# ZOWI_Main_Board_Booster.net
KiCad netlist of a schematic drawn in Altium Designer
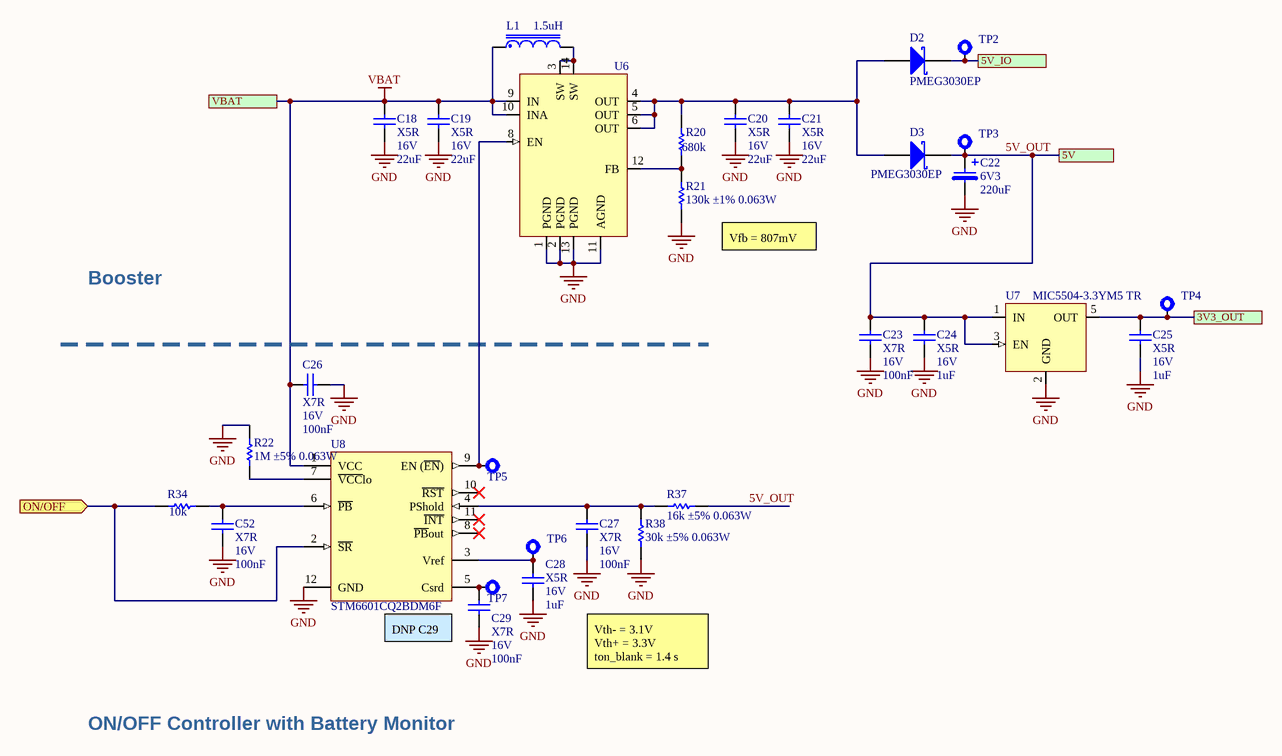
[diagram p0: ZOWI_Main_Board_Booster.SchDoc]

(export (version "E")
  (design (tool "Eeschema 10.0.6"))
  (components
    (comp (ref "C18")
      (value "Capacitor")
      (footprint "C0805")
      (description "Capacitor SMD")
      (fields
        (field (name "DIELECTRIC") "X5R")
        (field (name "VOLTAGE") "16V")
        (field (name "CAPACITANCE") "22uF")
        (field (name "PART NUMBER") "C0805_22uF_16V_±20%")
        (field (name "TOLERANCE") "±20%")
      )
      (libsource (lib "Pasives_Capacitor_SMD") (part "Capacitor"))
    )
    (comp (ref "C19")
      (value "Capacitor")
      (footprint "C0805")
      (description "Capacitor SMD")
      (fields
        (field (name "DIELECTRIC") "X5R")
        (field (name "VOLTAGE") "16V")
        (field (name "CAPACITANCE") "22uF")
        (field (name "PART NUMBER") "C0805_22uF_16V_±20%")
        (field (name "TOLERANCE") "±20%")
      )
      (libsource (lib "Pasives_Capacitor_SMD") (part "Capacitor"))
    )
    (comp (ref "C20")
      (value "Capacitor")
      (footprint "C0805")
      (description "Capacitor SMD")
      (fields
        (field (name "DIELECTRIC") "X5R")
        (field (name "VOLTAGE") "16V")
        (field (name "CAPACITANCE") "22uF")
        (field (name "PART NUMBER") "C0805_22uF_16V_±20%")
        (field (name "TOLERANCE") "±20%")
      )
      (libsource (lib "Pasives_Capacitor_SMD") (part "Capacitor"))
    )
    (comp (ref "C21")
      (value "Capacitor")
      (footprint "C0805")
      (description "Capacitor SMD")
      (fields
        (field (name "DIELECTRIC") "X5R")
        (field (name "VOLTAGE") "16V")
        (field (name "CAPACITANCE") "22uF")
        (field (name "PART NUMBER") "C0805_22uF_16V_±20%")
        (field (name "TOLERANCE") "±20%")
      )
      (libsource (lib "Pasives_Capacitor_SMD") (part "Capacitor"))
    )
    (comp (ref "C22")
      (value "Electrolytic")
      (footprint "CASE_D")
      (description "Capacitor, Electrolytic, SMD")
      (fields
        (field (name "VOLTAGE") "6V3")
        (field (name "CAPACITANCE") "220uF")
        (field (name "PART NUMBER") "Cap_Al_220uF_6V3")
        (field (name "MANUFACTURER") "Panasonic")
      )
      (libsource (lib "Pasives_Electrolytic_SMD") (part "Electrolytic"))
    )
    (comp (ref "C23")
      (value "Capacitor")
      (footprint "C0402")
      (description "Capacitor SMD")
      (fields
        (field (name "DIELECTRIC") "X7R")
        (field (name "VOLTAGE") "16V")
        (field (name "CAPACITANCE") "100nF")
        (field (name "PART NUMBER") "C0402_100nF_16V_±10%")
        (field (name "TOLERANCE") "±10%")
      )
      (libsource (lib "Pasives_Capacitor_SMD") (part "Capacitor"))
    )
    (comp (ref "C24")
      (value "Capacitor")
      (footprint "C0603")
      (description "Capacitor SMD")
      (fields
        (field (name "DIELECTRIC") "X5R")
        (field (name "VOLTAGE") "16V")
        (field (name "CAPACITANCE") "1uF")
        (field (name "PART NUMBER") "C0603_1uF_16V_±10%")
        (field (name "TOLERANCE") "±10%")
      )
      (libsource (lib "Pasives_Capacitor_SMD") (part "Capacitor"))
    )
    (comp (ref "C25")
      (value "Capacitor")
      (footprint "C0603")
      (description "Capacitor SMD")
      (fields
        (field (name "DIELECTRIC") "X5R")
        (field (name "VOLTAGE") "16V")
        (field (name "CAPACITANCE") "1uF")
        (field (name "PART NUMBER") "C0603_1uF_16V_±10%")
        (field (name "TOLERANCE") "±10%")
      )
      (libsource (lib "Pasives_Capacitor_SMD") (part "Capacitor"))
    )
    (comp (ref "C26")
      (value "Capacitor")
      (footprint "C0402")
      (description "Capacitor SMD")
      (fields
        (field (name "DIELECTRIC") "X7R")
        (field (name "VOLTAGE") "16V")
        (field (name "CAPACITANCE") "100nF")
        (field (name "PART NUMBER") "C0402_100nF_16V_±10%")
        (field (name "TOLERANCE") "±10%")
      )
      (libsource (lib "Pasives_Capacitor_SMD") (part "Capacitor"))
    )
    (comp (ref "C27")
      (value "Capacitor")
      (footprint "C0402")
      (description "Capacitor SMD")
      (fields
        (field (name "DIELECTRIC") "X7R")
        (field (name "VOLTAGE") "16V")
        (field (name "CAPACITANCE") "100nF")
        (field (name "PART NUMBER") "C0402_100nF_16V_±10%")
        (field (name "TOLERANCE") "±10%")
      )
      (libsource (lib "Pasives_Capacitor_SMD") (part "Capacitor"))
    )
    (comp (ref "C28")
      (value "Capacitor")
      (footprint "C0603")
      (description "Capacitor SMD")
      (fields
        (field (name "DIELECTRIC") "X5R")
        (field (name "VOLTAGE") "16V")
        (field (name "CAPACITANCE") "1uF")
        (field (name "PART NUMBER") "C0603_1uF_16V_±10%")
        (field (name "TOLERANCE") "±10%")
      )
      (libsource (lib "Pasives_Capacitor_SMD") (part "Capacitor"))
    )
    (comp (ref "C29")
      (value "Capacitor")
      (footprint "C0402")
      (description "Capacitor SMD")
      (fields
        (field (name "DIELECTRIC") "X7R")
        (field (name "VOLTAGE") "16V")
        (field (name "CAPACITANCE") "100nF")
        (field (name "PART NUMBER") "C0402_100nF_16V_±10%")
        (field (name "TOLERANCE") "±10%")
      )
      (libsource (lib "Pasives_Capacitor_SMD") (part "Capacitor"))
    )
    (comp (ref "C52")
      (value "Capacitor")
      (footprint "C0402")
      (description "Capacitor SMD")
      (fields
        (field (name "DIELECTRIC") "X7R")
        (field (name "VOLTAGE") "16V")
        (field (name "CAPACITANCE") "100nF")
        (field (name "PART NUMBER") "C0402_100nF_16V_±10%")
        (field (name "TOLERANCE") "±10%")
      )
      (libsource (lib "Pasives_Capacitor_SMD") (part "Capacitor"))
    )
    (comp (ref "D2")
      (value "PMEG3030EP")
      (footprint "SOD128")
      (description "Schottky Diode")
      (fields (field (name "MANUFACTURER") "NXP"))
      (libsource (lib "Semiconductors_Diodes") (part "Schottky"))
    )
    (comp (ref "D3")
      (value "PMEG3030EP")
      (footprint "SOD128")
      (description "Schottky Diode")
      (fields (field (name "MANUFACTURER") "NXP"))
      (libsource (lib "Semiconductors_Diodes") (part "Schottky"))
    )
    (comp (ref "L1")
      (value "SRN5040-1R5Y")
      (footprint "SRN5040")
      (description "Inductor, Power, SMD")
      (fields
        (field (name "PART NUMBER") "1.5uH_3,5A")
        (field (name "L") "1.5uH")
        (field (name "MANUFACTURER") "Bourns")
      )
      (libsource (lib "Pasivos_Inductor_SMD") (part "Power Inductor"))
    )
    (comp (ref "R20")
      (value "Resistor")
      (footprint "R0402")
      (description "Resistor, SMD")
      (fields
        (field (name "TOLERANCE") "±1%")
        (field (name "POWER") "0.063W")
        (field (name "RESISTANCE") "680k")
      )
      (libsource (lib "Pasives_Resistor_SMD") (part "Resistor"))
    )
    (comp (ref "R21")
      (value "130k ±1% 0.063W")
      (footprint "R0402")
      (description "Resistor, SMD")
      (fields (field (name "TOLERANCE") "±1%") (field (name "POWER") "0.063W"))
      (libsource (lib "Pasives_Resistor_SMD") (part "Resistor"))
    )
    (comp (ref "R22")
      (value "1M ±5% 0.063W")
      (footprint "R0402")
      (description "Resistor, SMD")
      (fields (field (name "TOLERANCE") "±5%") (field (name "POWER") "0.063W"))
      (libsource (lib "Pasives_Resistor_SMD") (part "Resistor"))
    )
    (comp (ref "R34")
      (value "Resistor")
      (footprint "R0402")
      (description "Resistor, SMD")
      (fields
        (field (name "TOLERANCE") "±5%")
        (field (name "POWER") "0.063W")
        (field (name "RESISTANCE") "10k")
      )
      (libsource (lib "Pasives_Resistor_SMD") (part "Resistor"))
    )
    (comp (ref "R37")
      (value "16k ±5% 0.063W")
      (footprint "R0402")
      (description "Resistor, SMD")
      (fields (field (name "TOLERANCE") "±5%") (field (name "POWER") "0.063W"))
      (libsource (lib "Pasives_Resistor_SMD") (part "Resistor"))
    )
    (comp (ref "R38")
      (value "30k ±5% 0.063W")
      (footprint "R0402")
      (description "Resistor, SMD")
      (fields (field (name "TOLERANCE") "±5%") (field (name "POWER") "0.063W"))
      (libsource (lib "Pasives_Resistor_SMD") (part "Resistor"))
    )
    (comp (ref "TP2")
      (value "Testpoint")
      (footprint "TP_SMD_1mm")
      (fields (field (name "MANUFACTURER") "Oxley") (field (name "PART NUMBER") "TP_SMD_1mm"))
      (libsource (lib "Miscelanea") (part "Testpoint"))
    )
    (comp (ref "TP3")
      (value "Testpoint")
      (footprint "TP_SMD_1mm")
      (fields (field (name "MANUFACTURER") "Oxley") (field (name "PART NUMBER") "TP_SMD_1mm"))
      (libsource (lib "Miscelanea") (part "Testpoint"))
    )
    (comp (ref "TP4")
      (value "Testpoint")
      (footprint "TP_SMD_1mm")
      (fields (field (name "MANUFACTURER") "Oxley") (field (name "PART NUMBER") "TP_SMD_1mm"))
      (libsource (lib "Miscelanea") (part "Testpoint"))
    )
    (comp (ref "TP5")
      (value "Testpoint")
      (footprint "TP_SMD_1mm")
      (fields (field (name "MANUFACTURER") "Oxley") (field (name "PART NUMBER") "TP_SMD_1mm"))
      (libsource (lib "Miscelanea") (part "Testpoint"))
    )
    (comp (ref "TP6")
      (value "Testpoint")
      (footprint "TP_SMD_1mm")
      (fields (field (name "MANUFACTURER") "Oxley") (field (name "PART NUMBER") "TP_SMD_1mm"))
      (libsource (lib "Miscelanea") (part "Testpoint"))
    )
    (comp (ref "TP7")
      (value "Testpoint")
      (footprint "TP_SMD_1mm")
      (fields (field (name "MANUFACTURER") "Oxley") (field (name "PART NUMBER") "TP_SMD_1mm"))
      (libsource (lib "Miscelanea") (part "Testpoint"))
    )
    (comp (ref "U6")
      (value "MP3421GG-Z")
      (footprint "QFN14_2X2")
      (description "Synchronous Boost Regulator with Bi-Directional Load Disconnect")
      (fields (field (name "PART NUMBER") "MP3421") (field (name "MANUFACTURER") "MPS"))
      (libsource (lib "Power_Regulator") (part "MP3421"))
    )
    (comp (ref "U7")
      (value "MIC5504-3.3YM5 TR")
      (footprint "SOT23-5")
      (description "LDO 300mA")
      (fields (field (name "PART NUMBER") "MIC5504-3.3") (field (name "MANUFACTURER") "Micrel"))
      (libsource (lib "Power_Regulator") (part "MIC550X"))
    )
    (comp (ref "U8")
      (value "STM6601")
      (footprint "TDFN12")
      (description "Smart push-button on/off controller")
      (fields
        (field (name "PART NUMBER") "STM6601CQ2BDM6F")
        (field (name "MANUFACTURER") "ST Microelectronics")
      )
      (libsource (lib "Power_Management") (part "STM6601"))
    )
  )
  (nets
    (net (code "1") (name "/3V3_OUT") (class "Default")
      (node (ref "C25") (pin "2") (pinfunction "2_2") (pintype "passive"))
      (node (ref "TP4") (pin "1") (pinfunction "1_1") (pintype "passive"))
      (node (ref "U7") (pin "5") (pinfunction "OUT_5") (pintype "passive"))
    )
    (net (code "2") (name "/5V_IO") (class "Default")
      (node (ref "D2") (pin "k") (pinfunction "K_k") (pintype "passive"))
      (node (ref "TP2") (pin "1") (pinfunction "1_1") (pintype "passive"))
    )
    (net (code "3") (name "/5V_OUT") (class "Default")
      (node (ref "C22") (pin "1") (pinfunction "1_1") (pintype "passive"))
      (node (ref "C23") (pin "2") (pinfunction "2_2") (pintype "passive"))
      (node (ref "C24") (pin "2") (pinfunction "2_2") (pintype "passive"))
      (node (ref "D3") (pin "k") (pinfunction "K_k") (pintype "passive"))
      (node (ref "R37") (pin "2") (pinfunction "2_2") (pintype "passive"))
      (node (ref "TP3") (pin "1") (pinfunction "1_1") (pintype "passive"))
      (node (ref "U7") (pin "1") (pinfunction "IN_1") (pintype "passive"))
      (node (ref "U7") (pin "3") (pinfunction "EN_3") (pintype "input"))
    )
    (net (code "4") (name "/ON{slash}OFF") (class "Default")
      (node (ref "R34") (pin "2") (pinfunction "2_2") (pintype "passive"))
      (node (ref "U8") (pin "2") (pinfunction "~{SR}_2") (pintype "input"))
    )
    (net (code "5") (name "GND") (class "Default")
      (node (ref "C18") (pin "1") (pinfunction "1_1") (pintype "passive"))
      (node (ref "C19") (pin "1") (pinfunction "1_1") (pintype "passive"))
      (node (ref "C20") (pin "1") (pinfunction "1_1") (pintype "passive"))
      (node (ref "C21") (pin "1") (pinfunction "1_1") (pintype "passive"))
      (node (ref "C22") (pin "2") (pinfunction "2_2") (pintype "passive"))
      (node (ref "C23") (pin "1") (pinfunction "1_1") (pintype "passive"))
      (node (ref "C24") (pin "1") (pinfunction "1_1") (pintype "passive"))
      (node (ref "C25") (pin "1") (pinfunction "1_1") (pintype "passive"))
      (node (ref "C26") (pin "2") (pinfunction "2_2") (pintype "passive"))
      (node (ref "C27") (pin "1") (pinfunction "1_1") (pintype "passive"))
      (node (ref "C28") (pin "1") (pinfunction "1_1") (pintype "passive"))
      (node (ref "C29") (pin "1") (pinfunction "1_1") (pintype "passive"))
      (node (ref "C52") (pin "1") (pinfunction "1_1") (pintype "passive"))
      (node (ref "R21") (pin "1") (pinfunction "1_1") (pintype "passive"))
      (node (ref "R22") (pin "1") (pinfunction "1_1") (pintype "passive"))
      (node (ref "R38") (pin "1") (pinfunction "1_1") (pintype "passive"))
      (node (ref "U6") (pin "1") (pinfunction "PGND_1") (pintype "passive"))
      (node (ref "U6") (pin "11") (pinfunction "AGND_11") (pintype "passive"))
      (node (ref "U6") (pin "13") (pinfunction "PGND_13") (pintype "passive"))
      (node (ref "U6") (pin "2") (pinfunction "PGND_2") (pintype "passive"))
      (node (ref "U7") (pin "2") (pinfunction "GND_2") (pintype "passive"))
      (node (ref "U8") (pin "12") (pinfunction "GND_12") (pintype "passive"))
    )
    (net (code "6") (name "Net-(C20-Pad2)") (class "Default")
      (node (ref "C20") (pin "2") (pinfunction "2_2") (pintype "passive"))
      (node (ref "C21") (pin "2") (pinfunction "2_2") (pintype "passive"))
      (node (ref "D2") (pin "A") (pinfunction "A_A") (pintype "passive"))
      (node (ref "D3") (pin "A") (pinfunction "A_A") (pintype "passive"))
      (node (ref "R20") (pin "2") (pinfunction "2_2") (pintype "passive"))
      (node (ref "U6") (pin "4") (pinfunction "OUT_4") (pintype "passive"))
      (node (ref "U6") (pin "5") (pinfunction "OUT_5") (pintype "passive"))
      (node (ref "U6") (pin "6") (pinfunction "OUT_6") (pintype "passive"))
    )
    (net (code "7") (name "Net-(L1-Pad2)") (class "Default")
      (node (ref "L1") (pin "2") (pinfunction "2_2") (pintype "passive"))
      (node (ref "U6") (pin "14") (pinfunction "SW_14") (pintype "passive"))
      (node (ref "U6") (pin "3") (pinfunction "SW_3") (pintype "passive"))
    )
    (net (code "8") (name "Net-(U6-EN)") (class "Default")
      (node (ref "TP5") (pin "1") (pinfunction "1_1") (pintype "passive"))
      (node (ref "U6") (pin "8") (pinfunction "EN_8") (pintype "input"))
      (node (ref "U8") (pin "9") (pinfunction "EN_(~{EN})_9") (pintype "output"))
    )
    (net (code "9") (name "Net-(U6-FB)") (class "Default")
      (node (ref "R20") (pin "1") (pinfunction "1_1") (pintype "passive"))
      (node (ref "R21") (pin "2") (pinfunction "2_2") (pintype "passive"))
      (node (ref "U6") (pin "12") (pinfunction "FB_12") (pintype "passive"))
    )
    (net (code "10") (name "Net-(U8-Csrd)") (class "Default")
      (node (ref "C29") (pin "2") (pinfunction "2_2") (pintype "passive"))
      (node (ref "TP7") (pin "1") (pinfunction "1_1") (pintype "passive"))
      (node (ref "U8") (pin "5") (pinfunction "Csrd_5") (pintype "passive"))
    )
    (net (code "11") (name "Net-(U8-PShold)") (class "Default")
      (node (ref "C27") (pin "2") (pinfunction "2_2") (pintype "passive"))
      (node (ref "R37") (pin "1") (pinfunction "1_1") (pintype "passive"))
      (node (ref "R38") (pin "2") (pinfunction "2_2") (pintype "passive"))
      (node (ref "U8") (pin "4") (pinfunction "PShold_4") (pintype "input"))
    )
    (net (code "12") (name "Net-(U8-Vref)") (class "Default")
      (node (ref "C28") (pin "2") (pinfunction "2_2") (pintype "passive"))
      (node (ref "TP6") (pin "1") (pinfunction "1_1") (pintype "passive"))
      (node (ref "U8") (pin "3") (pinfunction "Vref_3") (pintype "passive"))
    )
    (net (code "13") (name "Net-(U8-~{PB})") (class "Default")
      (node (ref "C52") (pin "2") (pinfunction "2_2") (pintype "passive"))
      (node (ref "R34") (pin "1") (pinfunction "1_1") (pintype "passive"))
      (node (ref "U8") (pin "6") (pinfunction "~{PB}_6") (pintype "input"))
    )
    (net (code "14") (name "Net-(U8-~{VCC}lo)") (class "Default")
      (node (ref "R22") (pin "2") (pinfunction "2_2") (pintype "passive"))
      (node (ref "U8") (pin "7") (pinfunction "~{VCC}lo_7") (pintype "passive"))
    )
    (net (code "15") (name "VBAT") (class "Default")
      (node (ref "C18") (pin "2") (pinfunction "2_2") (pintype "passive"))
      (node (ref "C19") (pin "2") (pinfunction "2_2") (pintype "passive"))
      (node (ref "C26") (pin "1") (pinfunction "1_1") (pintype "passive"))
      (node (ref "L1") (pin "1") (pinfunction "1_1") (pintype "passive"))
      (node (ref "U6") (pin "10") (pinfunction "INA_10") (pintype "passive"))
      (node (ref "U6") (pin "9") (pinfunction "IN_9") (pintype "passive"))
      (node (ref "U8") (pin "1") (pinfunction "VCC_1") (pintype "power_in"))
    )
    (net (code "16") (name "unconnected-(U8-~{INT}-Pad11)") (class "Default")
      (node (ref "U8") (pin "11") (pinfunction "~{INT}_11") (pintype "output+no_connect"))
    )
    (net (code "17") (name "unconnected-(U8-~{PB}out-Pad8)") (class "Default")
      (node (ref "U8") (pin "8") (pinfunction "~{PB}out_8") (pintype "output+no_connect"))
    )
    (net (code "18") (name "unconnected-(U8-~{RST}-Pad10)") (class "Default")
      (node (ref "U8") (pin "10") (pinfunction "~{RST}_10") (pintype "output+no_connect"))
    )
  )
)
